# modul.net
KiCad netlist of a schematic drawn in EAGLE
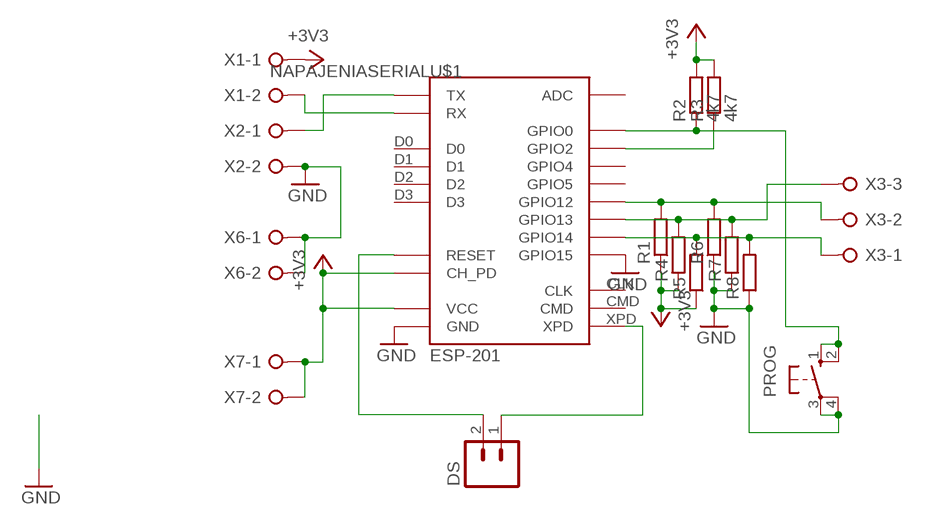
[diagram p0: schematic, sheet 1]

(export (version "E")
  (design (tool "Eeschema 10.0.6"))
  (components
    (comp (ref "DS")
      (value "M02")
      (footprint "eagle-import:02P")
      (libsource (lib "eagle-import") (part "M02"))
    )
    (comp (ref "PROG")
      (value "10-XX")
      (footprint "eagle-import:B3F-10XX")
      (fields (field (name "MPN") "B3F-1000"))
      (libsource (lib "eagle-import") (part "10-XX"))
    )
    (comp (ref "R1")
      (value "R-EU_0207/10")
      (footprint "eagle-import:0207_10")
      (libsource (lib "eagle-import") (part "R-EU_0207/10"))
    )
    (comp (ref "R2")
      (value "4k7")
      (footprint "eagle-import:0207_10")
      (libsource (lib "eagle-import") (part "R-EU_0207/10"))
    )
    (comp (ref "R3")
      (value "4k7")
      (footprint "eagle-import:0207_10")
      (libsource (lib "eagle-import") (part "R-EU_0207/10"))
    )
    (comp (ref "R4")
      (value "R-EU_0207/10")
      (footprint "eagle-import:0207_10")
      (libsource (lib "eagle-import") (part "R-EU_0207/10"))
    )
    (comp (ref "R5")
      (value "R-EU_0207/10")
      (footprint "eagle-import:0207_10")
      (libsource (lib "eagle-import") (part "R-EU_0207/10"))
    )
    (comp (ref "R6")
      (value "R-EU_0207/10")
      (footprint "eagle-import:0207_10")
      (libsource (lib "eagle-import") (part "R-EU_0207/10"))
    )
    (comp (ref "R7")
      (value "R-EU_0207/10")
      (footprint "eagle-import:0207_10")
      (libsource (lib "eagle-import") (part "R-EU_0207/10"))
    )
    (comp (ref "R8")
      (value "R-EU_0207/10")
      (footprint "eagle-import:0207_10")
      (libsource (lib "eagle-import") (part "R-EU_0207/10"))
    )
    (comp (ref "U$1")
      (value "ESP-201")
      (footprint "eagle-import:ESP-201")
      (libsource (lib "eagle-import") (part "ESP-201"))
    )
    (comp (ref "X1")
      (value "NAPAJENIASERIAL")
      (footprint "eagle-import:W237-132")
      (libsource (lib "eagle-import") (part "W237-02P"))
    )
    (comp (ref "X2")
      (value "W237-02P")
      (footprint "eagle-import:W237-132")
      (libsource (lib "eagle-import") (part "W237-02P"))
    )
    (comp (ref "X3")
      (value "W237-03P")
      (footprint "eagle-import:W237-133")
      (libsource (lib "eagle-import") (part "W237-03P"))
    )
    (comp (ref "X6")
      (value "W237-02P")
      (footprint "eagle-import:W237-132")
      (libsource (lib "eagle-import") (part "W237-02P"))
    )
    (comp (ref "X7")
      (value "W237-02P")
      (footprint "eagle-import:W237-132")
      (libsource (lib "eagle-import") (part "W237-02P"))
    )
  )
  (nets
    (net (code "1") (name "+3V3") (class "Default")
      (node (ref "R1") (pin "1") (pinfunction "1_1") (pintype "passive"))
      (node (ref "R2") (pin "2") (pinfunction "2_2") (pintype "passive"))
      (node (ref "R3") (pin "2") (pinfunction "2_2") (pintype "passive"))
      (node (ref "R4") (pin "1") (pinfunction "1_1") (pintype "passive"))
      (node (ref "R5") (pin "1") (pinfunction "1_1") (pintype "passive"))
      (node (ref "U$1") (pin "3V3") (pinfunction "VCC_3V3") (pintype "bidirectional"))
      (node (ref "U$1") (pin "3V3_2") (pinfunction "VCC_3V3_2") (pintype "bidirectional"))
      (node (ref "U$1") (pin "3V3_3") (pinfunction "VCC_3V3_3") (pintype "bidirectional"))
      (node (ref "U$1") (pin "CH_PD") (pinfunction "CH_PD_CH_PD") (pintype "bidirectional"))
      (node (ref "X1") (pin "1") (pinfunction "KL_1") (pintype "passive"))
      (node (ref "X7") (pin "1") (pinfunction "KL_1") (pintype "passive"))
      (node (ref "X7") (pin "2") (pinfunction "KL_2") (pintype "passive"))
    )
    (net (code "2") (name "GND") (class "Default")
      (node (ref "PROG") (pin "3") (pinfunction "P_3") (pintype "passive"))
      (node (ref "PROG") (pin "4") (pinfunction "P1_4") (pintype "passive"))
      (node (ref "R6") (pin "1") (pinfunction "1_1") (pintype "passive"))
      (node (ref "R7") (pin "1") (pinfunction "1_1") (pintype "passive"))
      (node (ref "R8") (pin "1") (pinfunction "1_1") (pintype "passive"))
      (node (ref "U$1") (pin "GND") (pinfunction "GND_GND") (pintype "bidirectional"))
      (node (ref "U$1") (pin "GND_2") (pinfunction "GND_GND_2") (pintype "bidirectional"))
      (node (ref "U$1") (pin "GND_3") (pinfunction "GND_GND_3") (pintype "bidirectional"))
      (node (ref "U$1") (pin "GPIO15") (pinfunction "GPIO15_GPIO15") (pintype "bidirectional"))
      (node (ref "X2") (pin "2") (pinfunction "KL_2") (pintype "passive"))
      (node (ref "X6") (pin "1") (pinfunction "KL_1") (pintype "passive"))
      (node (ref "X6") (pin "2") (pinfunction "KL_2") (pintype "passive"))
    )
    (net (code "3") (name "Net-(DS-Pad1)") (class "Default")
      (node (ref "DS") (pin "1") (pinfunction "1_1") (pintype "passive"))
      (node (ref "U$1") (pin "XPD") (pinfunction "XPD_XPD") (pintype "bidirectional"))
    )
    (net (code "4") (name "Net-(PROG-S)") (class "Default")
      (node (ref "PROG") (pin "1") (pinfunction "S_1") (pintype "passive"))
      (node (ref "PROG") (pin "2") (pinfunction "S1_2") (pintype "passive"))
      (node (ref "R2") (pin "1") (pinfunction "1_1") (pintype "passive"))
      (node (ref "U$1") (pin "GPIO0") (pinfunction "GPIO0_GPIO0") (pintype "bidirectional"))
    )
    (net (code "5") (name "Net-(R3-Pad1)") (class "Default")
      (node (ref "R3") (pin "1") (pinfunction "1_1") (pintype "passive"))
      (node (ref "U$1") (pin "GPIO2") (pinfunction "GPIO2_GPIO2") (pintype "bidirectional"))
    )
    (net (code "6") (name "Net-(U$1-RESET)") (class "Default")
      (node (ref "DS") (pin "2") (pinfunction "2_2") (pintype "passive"))
      (node (ref "U$1") (pin "RST") (pinfunction "RESET_RST") (pintype "bidirectional"))
    )
    (net (code "7") (name "Net-(X1B-KL)") (class "Default")
      (node (ref "U$1") (pin "RX") (pinfunction "RX_RX") (pintype "bidirectional"))
      (node (ref "X1") (pin "2") (pinfunction "KL_2") (pintype "passive"))
    )
    (net (code "8") (name "Net-(X2A-KL)") (class "Default")
      (node (ref "U$1") (pin "TX") (pinfunction "TX_TX") (pintype "bidirectional"))
      (node (ref "X2") (pin "1") (pinfunction "KL_1") (pintype "passive"))
    )
    (net (code "9") (name "Net-(X3A-KL)") (class "Default")
      (node (ref "R5") (pin "2") (pinfunction "2_2") (pintype "passive"))
      (node (ref "R8") (pin "2") (pinfunction "2_2") (pintype "passive"))
      (node (ref "U$1") (pin "GPIO14") (pinfunction "GPIO14_GPIO14") (pintype "bidirectional"))
      (node (ref "X3") (pin "1") (pinfunction "KL_1") (pintype "passive"))
    )
    (net (code "10") (name "Net-(X3B-KL)") (class "Default")
      (node (ref "R1") (pin "2") (pinfunction "2_2") (pintype "passive"))
      (node (ref "R6") (pin "2") (pinfunction "2_2") (pintype "passive"))
      (node (ref "U$1") (pin "GPIO12") (pinfunction "GPIO12_GPIO12") (pintype "bidirectional"))
      (node (ref "X3") (pin "2") (pinfunction "KL_2") (pintype "passive"))
    )
    (net (code "11") (name "Net-(X3C-KL)") (class "Default")
      (node (ref "R4") (pin "2") (pinfunction "2_2") (pintype "passive"))
      (node (ref "R7") (pin "2") (pinfunction "2_2") (pintype "passive"))
      (node (ref "U$1") (pin "GPIO13") (pinfunction "GPIO13_GPIO13") (pintype "bidirectional"))
      (node (ref "X3") (pin "3") (pinfunction "KL_3") (pintype "passive"))
    )
    (net (code "12") (name "unconnected-(U$1-PadADC)") (class "Default")
      (node (ref "U$1") (pin "ADC") (pinfunction "ADC_ADC") (pintype "bidirectional"))
    )
    (net (code "13") (name "unconnected-(U$1-PadCLK)") (class "Default")
      (node (ref "U$1") (pin "CLK") (pinfunction "CLK_CLK") (pintype "bidirectional"))
    )
    (net (code "14") (name "unconnected-(U$1-PadCMD)") (class "Default")
      (node (ref "U$1") (pin "CMD") (pinfunction "CMD_CMD") (pintype "bidirectional"))
    )
    (net (code "15") (name "unconnected-(U$1-PadD0)") (class "Default")
      (node (ref "U$1") (pin "D0") (pinfunction "D0_D0") (pintype "bidirectional"))
    )
    (net (code "16") (name "unconnected-(U$1-PadD1)") (class "Default")
      (node (ref "U$1") (pin "D1") (pinfunction "D1_D1") (pintype "bidirectional"))
    )
    (net (code "17") (name "unconnected-(U$1-PadD2)") (class "Default")
      (node (ref "U$1") (pin "D2") (pinfunction "D2_D2") (pintype "bidirectional"))
    )
    (net (code "18") (name "unconnected-(U$1-PadD3)") (class "Default")
      (node (ref "U$1") (pin "D3") (pinfunction "D3_D3") (pintype "bidirectional"))
    )
    (net (code "19") (name "unconnected-(U$1-PadGPIO4)") (class "Default")
      (node (ref "U$1") (pin "GPIO4") (pinfunction "GPIO4_GPIO4") (pintype "bidirectional"))
    )
    (net (code "20") (name "unconnected-(U$1-PadGPIO5)") (class "Default")
      (node (ref "U$1") (pin "GPIO5") (pinfunction "GPIO5_GPIO5") (pintype "bidirectional"))
    )
  )
)
